# Sheet2.net
KiCad netlist of a schematic drawn in Altium Designer
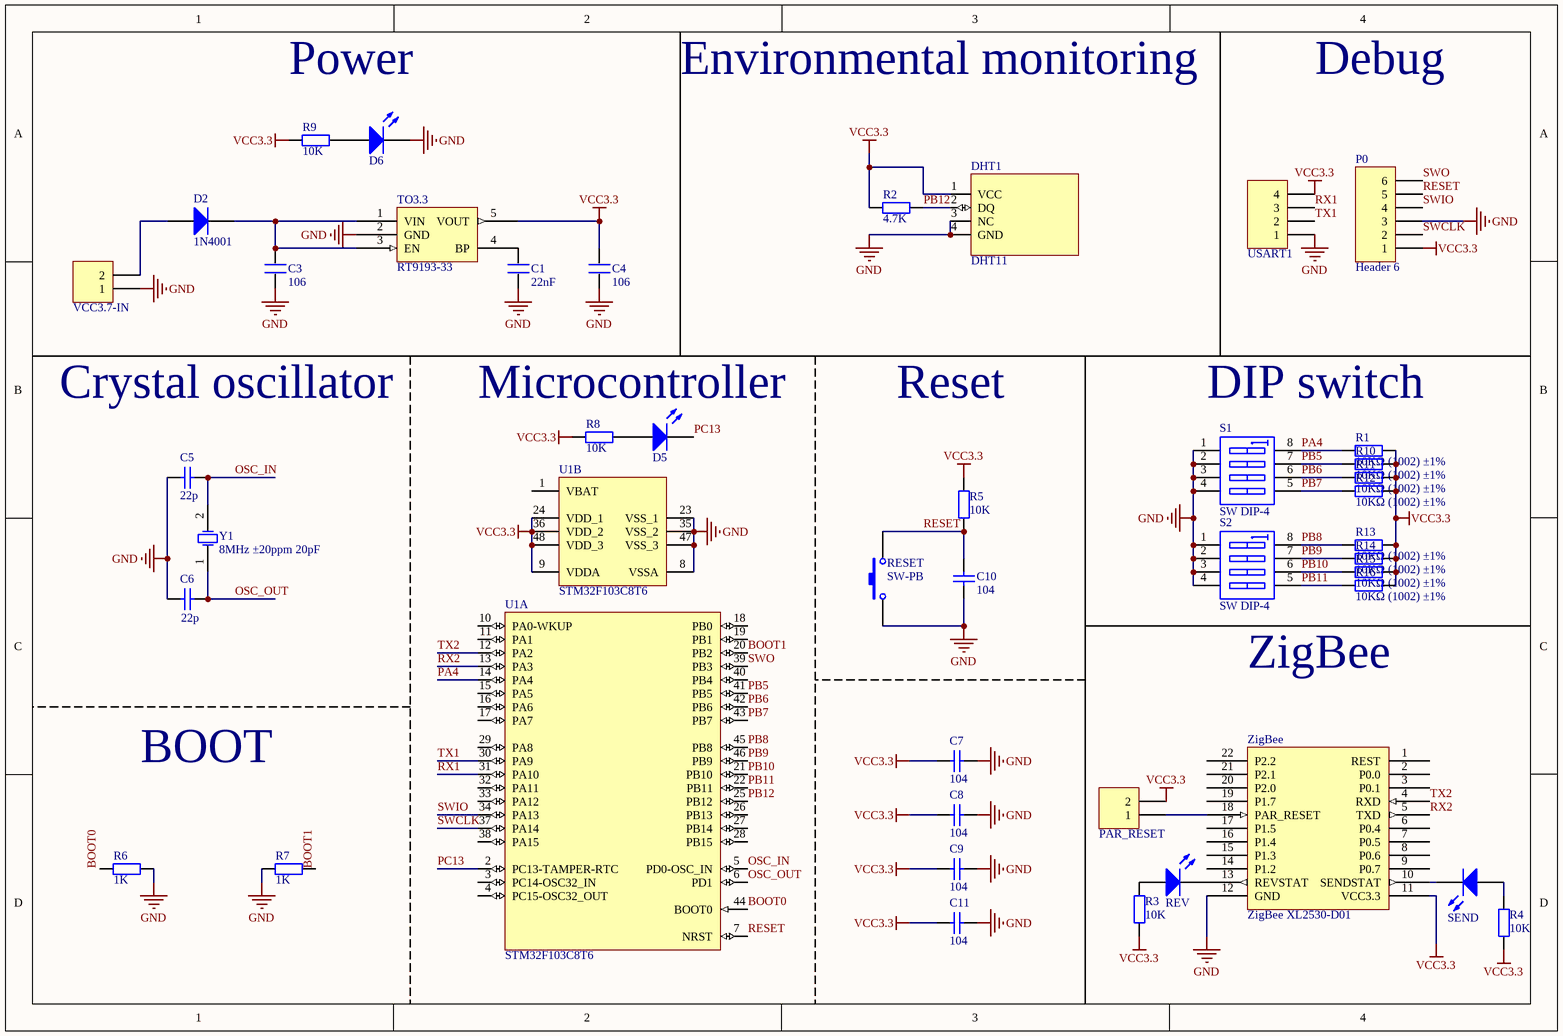
[diagram p0: Sheet2.SchDoc]

(export (version "E")
  (design (tool "Eeschema 10.0.6"))
  (components
    (comp (ref "C1") (value "22nF") (footprint "0805") (libsource (lib "阿波罗STM32F4&F7&H7底板封装库") (part "C")))
    (comp (ref "C3") (value "106") (footprint "0805") (libsource (lib "阿波罗STM32F4&F7&H7底板封装库") (part "C")))
    (comp (ref "C4") (value "106") (footprint "0805") (libsource (lib "阿波罗STM32F4&F7&H7底板封装库") (part "C")))
    (comp (ref "C5")
      (value "22p")
      (footprint "C-RAD-0805")
      (description "无极性电容")
      (fields (field (name "Comment") "Cap") (field (name "PUBLISHER") "Altium Limited"))
      (libsource (lib "ForSTM32") (part "Cap"))
    )
    (comp (ref "C6")
      (value "22p")
      (footprint "C-RAD-0805")
      (description "无极性电容")
      (fields (field (name "Comment") "Cap") (field (name "PUBLISHER") "Altium Limited"))
      (libsource (lib "ForSTM32") (part "Cap"))
    )
    (comp (ref "C7")
      (value "104")
      (footprint "C-RAD-0805")
      (description "无极性电容")
      (fields (field (name "Comment") "Cap") (field (name "PUBLISHER") "Altium Limited"))
      (libsource (lib "ForSTM32") (part "Cap"))
    )
    (comp (ref "C8")
      (value "104")
      (footprint "C-RAD-0805")
      (description "无极性电容")
      (fields (field (name "Comment") "Cap") (field (name "PUBLISHER") "Altium Limited"))
      (libsource (lib "ForSTM32") (part "Cap"))
    )
    (comp (ref "C9")
      (value "104")
      (footprint "C-RAD-0805")
      (description "无极性电容")
      (fields (field (name "Comment") "Cap") (field (name "PUBLISHER") "Altium Limited"))
      (libsource (lib "ForSTM32") (part "Cap"))
    )
    (comp (ref "C10")
      (value "104")
      (footprint "C-RAD-0805")
      (description "无极性电容")
      (fields (field (name "Comment") "Cap") (field (name "PUBLISHER") "Altium Limited"))
      (libsource (lib "ForSTM32") (part "Cap"))
    )
    (comp (ref "C11")
      (value "104")
      (footprint "C-RAD-0805")
      (description "无极性电容")
      (fields (field (name "Comment") "Cap") (field (name "PUBLISHER") "Altium Limited"))
      (libsource (lib "ForSTM32") (part "Cap"))
    )
    (comp (ref "D2")
      (value "Diode")
      (footprint "DIODE-1206")
      (description "二极管")
      (fields (field (name "TYPE") "1N4001") (field (name "PUBLISHER") "Altium Limited"))
      (libsource (lib "ForSTM32") (part "Diode"))
    )
    (comp (ref "D5")
      (value "LED0")
      (footprint "LED_0805")
      (description "发光二极管")
      (fields (field (name "PUBLISHER") "Altium Limited"))
      (libsource (lib "ForSTM32") (part "LED0"))
    )
    (comp (ref "D6")
      (value "LED0")
      (footprint "LED_0805")
      (description "发光二极管")
      (fields (field (name "PUBLISHER") "Altium Limited"))
      (libsource (lib "ForSTM32") (part "LED0"))
    )
    (comp (ref "DHT1") (value "DHT11") (footprint "DTH11") (libsource (lib "我的元件库") (part "DHT11")))
    (comp (ref "P0")
      (value "Header 6")
      (footprint "HDR1X6")
      (description "Header, 6-Pin")
      (fields (field (name "PUBLISHER") "Altium Limited"))
      (libsource (lib "Miscellaneous Connectors") (part "Header 6"))
    )
    (comp (ref "PAR_RESET")
      (value "Header 2")
      (footprint "HDR2X1_A")
      (description "接插件")
      (fields (field (name "PUBLISHER") "Altium Limited"))
      (libsource (lib "ForSTM32") (part "Header 2"))
    )
    (comp (ref "R1")
      (value "10KΩ (1002) ±1%")
      (footprint "0805_R")
      (description "贴片电阻")
      (libsource (lib "Miscellaneous Devices LC") (part "0805 10KΩ (1002) 1%"))
    )
    (comp (ref "R2")
      (value "4.7K")
      (footprint "0805-1")
      (description "贴片电阻")
      (fields (field (name "Comment") "Res1") (field (name "PUBLISHER") "Altium Limited"))
      (libsource (lib "ForSTM32") (part "Res1"))
    )
    (comp (ref "R3")
      (value "10K")
      (footprint "0805-1")
      (description "贴片电阻")
      (fields (field (name "Comment") "Res1") (field (name "PUBLISHER") "Altium Limited"))
      (libsource (lib "") (part "Res1_1"))
    )
    (comp (ref "R4")
      (value "10K")
      (footprint "0805-1")
      (description "贴片电阻")
      (fields (field (name "Comment") "Res1") (field (name "PUBLISHER") "Altium Limited"))
      (libsource (lib "") (part "Res1_1"))
    )
    (comp (ref "R5")
      (value "10K")
      (footprint "0805-1")
      (description "贴片电阻")
      (fields (field (name "Comment") "Res1") (field (name "PUBLISHER") "Altium Limited"))
      (libsource (lib "") (part "Res1_1"))
    )
    (comp (ref "R6")
      (value "1K")
      (footprint "0805-1")
      (description "贴片电阻")
      (fields (field (name "Comment") "Res1") (field (name "PUBLISHER") "Altium Limited"))
      (libsource (lib "ForSTM32") (part "Res1"))
    )
    (comp (ref "R7")
      (value "1K")
      (footprint "0805-1")
      (description "贴片电阻")
      (fields (field (name "Comment") "Res1") (field (name "PUBLISHER") "Altium Limited"))
      (libsource (lib "ForSTM32") (part "Res1"))
    )
    (comp (ref "R8")
      (value "10K")
      (footprint "0805-1")
      (description "贴片电阻")
      (fields (field (name "Comment") "Res1") (field (name "PUBLISHER") "Altium Limited"))
      (libsource (lib "ForSTM32") (part "Res1"))
    )
    (comp (ref "R9")
      (value "10K")
      (footprint "0805-1")
      (description "贴片电阻")
      (fields (field (name "Comment") "Res1") (field (name "PUBLISHER") "Altium Limited"))
      (libsource (lib "ForSTM32") (part "Res1"))
    )
    (comp (ref "R10")
      (value "10KΩ (1002) ±1%")
      (footprint "0805_R")
      (description "贴片电阻")
      (libsource (lib "Miscellaneous Devices LC") (part "0805 10KΩ (1002) 1%"))
    )
    (comp (ref "R11")
      (value "10KΩ (1002) ±1%")
      (footprint "0805_R")
      (description "贴片电阻")
      (libsource (lib "Miscellaneous Devices LC") (part "0805 10KΩ (1002) 1%"))
    )
    (comp (ref "R12")
      (value "10KΩ (1002) ±1%")
      (footprint "0805_R")
      (description "贴片电阻")
      (libsource (lib "Miscellaneous Devices LC") (part "0805 10KΩ (1002) 1%"))
    )
    (comp (ref "R13")
      (value "10KΩ (1002) ±1%")
      (footprint "0805_R")
      (description "贴片电阻")
      (libsource (lib "Miscellaneous Devices LC") (part "0805 10KΩ (1002) 1%"))
    )
    (comp (ref "R14")
      (value "10KΩ (1002) ±1%")
      (footprint "0805_R")
      (description "贴片电阻")
      (libsource (lib "Miscellaneous Devices LC") (part "0805 10KΩ (1002) 1%"))
    )
    (comp (ref "R15")
      (value "10KΩ (1002) ±1%")
      (footprint "0805_R")
      (description "贴片电阻")
      (libsource (lib "Miscellaneous Devices LC") (part "0805 10KΩ (1002) 1%"))
    )
    (comp (ref "R16")
      (value "10KΩ (1002) ±1%")
      (footprint "0805_R")
      (description "贴片电阻")
      (libsource (lib "Miscellaneous Devices LC") (part "0805 10KΩ (1002) 1%"))
    )
    (comp (ref "RESET")
      (value "SW-PB")
      (footprint "SW_PB2_A1")
      (description "微动开关")
      (fields (field (name "PUBLISHER") "Altium Limited"))
      (libsource (lib "ForSTM32") (part "SW-PB"))
    )
    (comp (ref "REV")
      (value "LED0")
      (footprint "LED_0805")
      (description "发光二极管")
      (fields (field (name "PUBLISHER") "Altium Limited"))
      (libsource (lib "ForSTM32") (part "LED0"))
    )
    (comp (ref "S1")
      (value "SW DIP-4")
      (footprint "SO8_xl")
      (description "DIP Switch, 4 Position, SPST")
      (fields (field (name "PUBLISHER") "Altium Limited"))
      (libsource (lib "Miscellaneous Devices") (part "SW DIP-4"))
    )
    (comp (ref "S2")
      (value "SW DIP-4")
      (footprint "SO8_xl")
      (description "DIP Switch, 4 Position, SPST")
      (fields (field (name "PUBLISHER") "Altium Limited"))
      (libsource (lib "Miscellaneous Devices") (part "SW DIP-4"))
    )
    (comp (ref "SEND")
      (value "LED0")
      (footprint "LED_0805")
      (description "发光二极管")
      (fields (field (name "PUBLISHER") "Altium Limited"))
      (libsource (lib "ForSTM32") (part "LED0"))
    )
    (comp (ref "TO3.3")
      (value "RT9193-33")
      (footprint "LC-SOT-23-5")
      (libsource (lib "我的元件库") (part "RT9193-33"))
    )
    (comp (ref "U1")
      (value "STM32F103C8T6")
      (footprint "LQFP-48_7x7x05P")
      (description "ARM")
      (libsource (lib "Miscellaneous Devices LC") (part "STM32F103C8T6"))
    )
    (comp (ref "USART1")
      (value "Header 4")
      (footprint "HDR4X1_A")
      (description "接插件")
      (fields (field (name "PUBLISHER") "Altium Limited"))
      (libsource (lib "ForSTM32") (part "Header 4"))
    )
    (comp (ref "VCC3.7-IN")
      (value "Header 2")
      (footprint "HDR2X1_A")
      (description "接插件")
      (fields (field (name "PUBLISHER") "Altium Limited"))
      (libsource (lib "ForSTM32") (part "Header 2"))
    )
    (comp (ref "Y1")
      (value "8MHz ±20ppm 20pF")
      (footprint "SMD-5032_2P")
      (description "贴片晶振")
      (libsource (lib "Miscellaneous Devices LC") (part "SMD-5032_2P 8MHz 20ppm 20pF"))
    )
    (comp (ref "ZigBee")
      (value "ZigBee XL2530-D01")
      (footprint "ZigBeeXL2530-D01")
      (libsource (lib "我的元件库") (part "ZigBee XL2530-D01"))
    )
  )
  (nets
    (net (code "1") (name "/BOOT0") (class "Default")
      (node (ref "R6") (pin "1") (pinfunction "1_1") (pintype "passive"))
      (node (ref "U1") (pin "44") (pinfunction "BOOT0_44") (pintype "input"))
    )
    (net (code "2") (name "/BOOT1") (class "Default")
      (node (ref "R7") (pin "2") (pinfunction "2_2") (pintype "passive"))
      (node (ref "U1") (pin "20") (pinfunction "PB2_20") (pintype "bidirectional"))
    )
    (net (code "3") (name "/OSC_IN") (class "Default")
      (node (ref "C5") (pin "2") (pinfunction "2_2") (pintype "passive"))
      (node (ref "U1") (pin "5") (pinfunction "PD0-OSC_IN_5") (pintype "bidirectional"))
      (node (ref "Y1") (pin "2") (pinfunction "OSC2_2") (pintype "passive"))
    )
    (net (code "4") (name "/OSC_OUT") (class "Default")
      (node (ref "C6") (pin "2") (pinfunction "2_2") (pintype "passive"))
      (node (ref "U1") (pin "6") (pinfunction "PD1_6") (pintype "bidirectional"))
      (node (ref "Y1") (pin "1") (pinfunction "OSC1_1") (pintype "passive"))
    )
    (net (code "5") (name "/PA4") (class "Default")
      (node (ref "R1") (pin "1") (pinfunction "1_1") (pintype "passive"))
      (node (ref "S1") (pin "8") (pinfunction "B1_8") (pintype "passive"))
      (node (ref "U1") (pin "14") (pinfunction "PA4_14") (pintype "bidirectional"))
    )
    (net (code "6") (name "/PB5") (class "Default")
      (node (ref "R10") (pin "1") (pinfunction "1_1") (pintype "passive"))
      (node (ref "S1") (pin "7") (pinfunction "B2_7") (pintype "passive"))
      (node (ref "U1") (pin "41") (pinfunction "PB5_41") (pintype "bidirectional"))
    )
    (net (code "7") (name "/PB6") (class "Default")
      (node (ref "R11") (pin "1") (pinfunction "1_1") (pintype "passive"))
      (node (ref "S1") (pin "6") (pinfunction "B3_6") (pintype "passive"))
      (node (ref "U1") (pin "42") (pinfunction "PB6_42") (pintype "bidirectional"))
    )
    (net (code "8") (name "/PB7") (class "Default")
      (node (ref "R12") (pin "1") (pinfunction "1_1") (pintype "passive"))
      (node (ref "S1") (pin "5") (pinfunction "B4_5") (pintype "passive"))
      (node (ref "U1") (pin "43") (pinfunction "PB7_43") (pintype "bidirectional"))
    )
    (net (code "9") (name "/PB8") (class "Default")
      (node (ref "R13") (pin "1") (pinfunction "1_1") (pintype "passive"))
      (node (ref "S2") (pin "8") (pinfunction "B1_8") (pintype "passive"))
      (node (ref "U1") (pin "45") (pinfunction "PB8_45") (pintype "bidirectional"))
    )
    (net (code "10") (name "/PB9") (class "Default")
      (node (ref "R14") (pin "1") (pinfunction "1_1") (pintype "passive"))
      (node (ref "S2") (pin "7") (pinfunction "B2_7") (pintype "passive"))
      (node (ref "U1") (pin "46") (pinfunction "PB9_46") (pintype "bidirectional"))
    )
    (net (code "11") (name "/PB10") (class "Default")
      (node (ref "R15") (pin "1") (pinfunction "1_1") (pintype "passive"))
      (node (ref "S2") (pin "6") (pinfunction "B3_6") (pintype "passive"))
      (node (ref "U1") (pin "21") (pinfunction "PB10_21") (pintype "bidirectional"))
    )
    (net (code "12") (name "/PB11") (class "Default")
      (node (ref "R16") (pin "1") (pinfunction "1_1") (pintype "passive"))
      (node (ref "S2") (pin "5") (pinfunction "B4_5") (pintype "passive"))
      (node (ref "U1") (pin "22") (pinfunction "PB11_22") (pintype "bidirectional"))
    )
    (net (code "13") (name "/PB12") (class "Default")
      (node (ref "DHT1") (pin "2") (pinfunction "DQ_2") (pintype "bidirectional"))
      (node (ref "R2") (pin "2") (pinfunction "2_2") (pintype "passive"))
      (node (ref "U1") (pin "25") (pinfunction "PB12_25") (pintype "bidirectional"))
    )
    (net (code "14") (name "/PC13") (class "Default")
      (node (ref "D5") (pin "2") (pinfunction "K_2") (pintype "passive"))
      (node (ref "U1") (pin "2") (pinfunction "PC13-TAMPER-RTC_2") (pintype "bidirectional"))
    )
    (net (code "15") (name "/RESET") (class "Default")
      (node (ref "C10") (pin "1") (pinfunction "1_1") (pintype "passive"))
      (node (ref "P0") (pin "5") (pinfunction "5_5") (pintype "passive"))
      (node (ref "R5") (pin "1") (pinfunction "1_1") (pintype "passive"))
      (node (ref "RESET") (pin "2") (pinfunction "2_2") (pintype "passive"))
      (node (ref "U1") (pin "7") (pinfunction "NRST_7") (pintype "bidirectional"))
    )
    (net (code "16") (name "/RX1") (class "Default")
      (node (ref "U1") (pin "31") (pinfunction "PA10_31") (pintype "bidirectional"))
      (node (ref "USART1") (pin "3") (pinfunction "3_3") (pintype "passive"))
    )
    (net (code "17") (name "/RX2") (class "Default")
      (node (ref "U1") (pin "13") (pinfunction "PA3_13") (pintype "bidirectional"))
      (node (ref "ZigBee") (pin "5") (pinfunction "TXD_5") (pintype "output"))
    )
    (net (code "18") (name "/SWCLK") (class "Default")
      (node (ref "P0") (pin "2") (pinfunction "2_2") (pintype "passive"))
      (node (ref "U1") (pin "37") (pinfunction "PA14_37") (pintype "bidirectional"))
    )
    (net (code "19") (name "/SWIO") (class "Default")
      (node (ref "P0") (pin "4") (pinfunction "4_4") (pintype "passive"))
      (node (ref "U1") (pin "34") (pinfunction "PA13_34") (pintype "bidirectional"))
    )
    (net (code "20") (name "/SWO") (class "Default")
      (node (ref "P0") (pin "6") (pinfunction "6_6") (pintype "passive"))
      (node (ref "U1") (pin "39") (pinfunction "PB3_39") (pintype "bidirectional"))
    )
    (net (code "21") (name "/TX1") (class "Default")
      (node (ref "U1") (pin "30") (pinfunction "PA9_30") (pintype "bidirectional"))
      (node (ref "USART1") (pin "2") (pinfunction "2_2") (pintype "passive"))
    )
    (net (code "22") (name "/TX2") (class "Default")
      (node (ref "U1") (pin "12") (pinfunction "PA2_12") (pintype "bidirectional"))
      (node (ref "ZigBee") (pin "4") (pinfunction "RXD_4") (pintype "input"))
    )
    (net (code "23") (name "GND") (class "Default")
      (node (ref "C1") (pin "1") (pintype "passive"))
      (node (ref "C10") (pin "2") (pinfunction "2_2") (pintype "passive"))
      (node (ref "C11") (pin "2") (pinfunction "2_2") (pintype "passive"))
      (node (ref "C3") (pin "2") (pintype "passive"))
      (node (ref "C4") (pin "1") (pintype "passive"))
      (node (ref "C5") (pin "1") (pinfunction "1_1") (pintype "passive"))
      (node (ref "C6") (pin "1") (pinfunction "1_1") (pintype "passive"))
      (node (ref "C7") (pin "2") (pinfunction "2_2") (pintype "passive"))
      (node (ref "C8") (pin "2") (pinfunction "2_2") (pintype "passive"))
      (node (ref "C9") (pin "2") (pinfunction "2_2") (pintype "passive"))
      (node (ref "D6") (pin "2") (pinfunction "K_2") (pintype "passive"))
      (node (ref "DHT1") (pin "3") (pinfunction "NC_3") (pintype "passive"))
      (node (ref "DHT1") (pin "4") (pinfunction "GND_4") (pintype "power_in"))
      (node (ref "P0") (pin "3") (pinfunction "3_3") (pintype "passive"))
      (node (ref "R6") (pin "2") (pinfunction "2_2") (pintype "passive"))
      (node (ref "R7") (pin "1") (pinfunction "1_1") (pintype "passive"))
      (node (ref "RESET") (pin "1") (pinfunction "1_1") (pintype "passive"))
      (node (ref "S1") (pin "1") (pinfunction "A1_1") (pintype "passive"))
      (node (ref "S1") (pin "2") (pinfunction "A2_2") (pintype "passive"))
      (node (ref "S1") (pin "3") (pinfunction "A3_3") (pintype "passive"))
      (node (ref "S1") (pin "4") (pinfunction "A4_4") (pintype "passive"))
      (node (ref "S2") (pin "1") (pinfunction "A1_1") (pintype "passive"))
      (node (ref "S2") (pin "2") (pinfunction "A2_2") (pintype "passive"))
      (node (ref "S2") (pin "3") (pinfunction "A3_3") (pintype "passive"))
      (node (ref "S2") (pin "4") (pinfunction "A4_4") (pintype "passive"))
      (node (ref "TO3.3") (pin "2") (pinfunction "GND_2") (pintype "power_in"))
      (node (ref "U1") (pin "23") (pinfunction "VSS_1_23") (pintype "power_in"))
      (node (ref "U1") (pin "35") (pinfunction "VSS_2_35") (pintype "power_in"))
      (node (ref "U1") (pin "47") (pinfunction "VSS_3_47") (pintype "power_in"))
      (node (ref "U1") (pin "8") (pinfunction "VSSA_8") (pintype "power_in"))
      (node (ref "USART1") (pin "1") (pinfunction "1_1") (pintype "passive"))
      (node (ref "VCC3.7-IN") (pin "1") (pinfunction "1_1") (pintype "passive"))
      (node (ref "ZigBee") (pin "12") (pinfunction "GND_12") (pintype "passive"))
    )
    (net (code "24") (name "Net-(D2-A)") (class "Default")
      (node (ref "D2") (pin "1") (pinfunction "A_1") (pintype "passive"))
      (node (ref "VCC3.7-IN") (pin "2") (pinfunction "2_2") (pintype "passive"))
    )
    (net (code "25") (name "Net-(D2-K)") (class "Default")
      (node (ref "C3") (pin "1") (pintype "passive"))
      (node (ref "D2") (pin "2") (pinfunction "K_2") (pintype "passive"))
      (node (ref "TO3.3") (pin "1") (pinfunction "VIN_1") (pintype "power_in"))
      (node (ref "TO3.3") (pin "3") (pinfunction "EN_3") (pintype "input"))
    )
    (net (code "26") (name "Net-(D5-A)") (class "Default")
      (node (ref "D5") (pin "1") (pinfunction "A_1") (pintype "passive"))
      (node (ref "R8") (pin "2") (pinfunction "2_2") (pintype "passive"))
    )
    (net (code "27") (name "Net-(D6-A)") (class "Default")
      (node (ref "D6") (pin "1") (pinfunction "A_1") (pintype "passive"))
      (node (ref "R9") (pin "2") (pinfunction "2_2") (pintype "passive"))
    )
    (net (code "28") (name "Net-(REV-A)") (class "Default")
      (node (ref "R3") (pin "2") (pinfunction "2_2") (pintype "passive"))
      (node (ref "REV") (pin "1") (pinfunction "A_1") (pintype "passive"))
    )
    (net (code "29") (name "Net-(REV-K)") (class "Default")
      (node (ref "REV") (pin "2") (pinfunction "K_2") (pintype "passive"))
      (node (ref "ZigBee") (pin "13") (pinfunction "REVSTAT_13") (pintype "output"))
    )
    (net (code "30") (name "Net-(SEND-A)") (class "Default")
      (node (ref "R4") (pin "2") (pinfunction "2_2") (pintype "passive"))
      (node (ref "SEND") (pin "1") (pinfunction "A_1") (pintype "passive"))
    )
    (net (code "31") (name "Net-(SEND-K)") (class "Default")
      (node (ref "SEND") (pin "2") (pinfunction "K_2") (pintype "passive"))
      (node (ref "ZigBee") (pin "10") (pinfunction "SENDSTAT_10") (pintype "output"))
    )
    (net (code "32") (name "Net-(TO3.3-BP)") (class "Default")
      (node (ref "C1") (pin "2") (pintype "passive"))
      (node (ref "TO3.3") (pin "4") (pinfunction "BP_4") (pintype "passive"))
    )
    (net (code "33") (name "Net-(ZigBee-PAR_RESET)") (class "Default")
      (node (ref "PAR_RESET") (pin "1") (pinfunction "1_1") (pintype "passive"))
      (node (ref "ZigBee") (pin "18") (pinfunction "PAR_RESET_18") (pintype "input"))
    )
    (net (code "34") (name "VCC3.3") (class "Default")
      (node (ref "C11") (pin "1") (pinfunction "1_1") (pintype "passive"))
      (node (ref "C4") (pin "2") (pintype "passive"))
      (node (ref "C7") (pin "1") (pinfunction "1_1") (pintype "passive"))
      (node (ref "C8") (pin "1") (pinfunction "1_1") (pintype "passive"))
      (node (ref "C9") (pin "1") (pinfunction "1_1") (pintype "passive"))
      (node (ref "DHT1") (pin "1") (pinfunction "VCC_1") (pintype "power_in"))
      (node (ref "P0") (pin "1") (pinfunction "1_1") (pintype "passive"))
      (node (ref "PAR_RESET") (pin "2") (pinfunction "2_2") (pintype "passive"))
      (node (ref "R1") (pin "2") (pinfunction "2_2") (pintype "passive"))
      (node (ref "R10") (pin "2") (pinfunction "2_2") (pintype "passive"))
      (node (ref "R11") (pin "2") (pinfunction "2_2") (pintype "passive"))
      (node (ref "R12") (pin "2") (pinfunction "2_2") (pintype "passive"))
      (node (ref "R13") (pin "2") (pinfunction "2_2") (pintype "passive"))
      (node (ref "R14") (pin "2") (pinfunction "2_2") (pintype "passive"))
      (node (ref "R15") (pin "2") (pinfunction "2_2") (pintype "passive"))
      (node (ref "R16") (pin "2") (pinfunction "2_2") (pintype "passive"))
      (node (ref "R2") (pin "1") (pinfunction "1_1") (pintype "passive"))
      (node (ref "R3") (pin "1") (pinfunction "1_1") (pintype "passive"))
      (node (ref "R4") (pin "1") (pinfunction "1_1") (pintype "passive"))
      (node (ref "R5") (pin "2") (pinfunction "2_2") (pintype "passive"))
      (node (ref "R8") (pin "1") (pinfunction "1_1") (pintype "passive"))
      (node (ref "R9") (pin "1") (pinfunction "1_1") (pintype "passive"))
      (node (ref "TO3.3") (pin "5") (pinfunction "VOUT_5") (pintype "output"))
      (node (ref "U1") (pin "24") (pinfunction "VDD_1_24") (pintype "power_in"))
      (node (ref "U1") (pin "36") (pinfunction "VDD_2_36") (pintype "power_in"))
      (node (ref "U1") (pin "48") (pinfunction "VDD_3_48") (pintype "power_in"))
      (node (ref "U1") (pin "9") (pinfunction "VDDA_9") (pintype "power_in"))
      (node (ref "USART1") (pin "4") (pinfunction "4_4") (pintype "passive"))
      (node (ref "ZigBee") (pin "11") (pinfunction "VCC3.3_11") (pintype "passive"))
    )
    (net (code "35") (name "unconnected-(U1A-PA0-WKUP-Pad10)") (class "Default")
      (node (ref "U1") (pin "10") (pinfunction "PA0-WKUP_10") (pintype "bidirectional"))
    )
    (net (code "36") (name "unconnected-(U1A-PA1-Pad11)") (class "Default")
      (node (ref "U1") (pin "11") (pinfunction "PA1_11") (pintype "bidirectional"))
    )
    (net (code "37") (name "unconnected-(U1A-PA5-Pad15)") (class "Default")
      (node (ref "U1") (pin "15") (pinfunction "PA5_15") (pintype "bidirectional"))
    )
    (net (code "38") (name "unconnected-(U1A-PA6-Pad16)") (class "Default")
      (node (ref "U1") (pin "16") (pinfunction "PA6_16") (pintype "bidirectional"))
    )
    (net (code "39") (name "unconnected-(U1A-PA7-Pad17)") (class "Default")
      (node (ref "U1") (pin "17") (pinfunction "PA7_17") (pintype "bidirectional"))
    )
    (net (code "40") (name "unconnected-(U1A-PA8-Pad29)") (class "Default")
      (node (ref "U1") (pin "29") (pinfunction "PA8_29") (pintype "bidirectional"))
    )
    (net (code "41") (name "unconnected-(U1A-PA11-Pad32)") (class "Default")
      (node (ref "U1") (pin "32") (pinfunction "PA11_32") (pintype "bidirectional"))
    )
    (net (code "42") (name "unconnected-(U1A-PA12-Pad33)") (class "Default")
      (node (ref "U1") (pin "33") (pinfunction "PA12_33") (pintype "bidirectional"))
    )
    (net (code "43") (name "unconnected-(U1A-PA15-Pad38)") (class "Default")
      (node (ref "U1") (pin "38") (pinfunction "PA15_38") (pintype "bidirectional"))
    )
    (net (code "44") (name "unconnected-(U1A-PB0-Pad18)") (class "Default")
      (node (ref "U1") (pin "18") (pinfunction "PB0_18") (pintype "bidirectional"))
    )
    (net (code "45") (name "unconnected-(U1A-PB1-Pad19)") (class "Default")
      (node (ref "U1") (pin "19") (pinfunction "PB1_19") (pintype "bidirectional"))
    )
    (net (code "46") (name "unconnected-(U1A-PB4-Pad40)") (class "Default")
      (node (ref "U1") (pin "40") (pinfunction "PB4_40") (pintype "bidirectional"))
    )
    (net (code "47") (name "unconnected-(U1A-PB13-Pad26)") (class "Default")
      (node (ref "U1") (pin "26") (pinfunction "PB13_26") (pintype "bidirectional"))
    )
    (net (code "48") (name "unconnected-(U1A-PB14-Pad27)") (class "Default")
      (node (ref "U1") (pin "27") (pinfunction "PB14_27") (pintype "bidirectional"))
    )
    (net (code "49") (name "unconnected-(U1A-PB15-Pad28)") (class "Default")
      (node (ref "U1") (pin "28") (pinfunction "PB15_28") (pintype "bidirectional"))
    )
    (net (code "50") (name "unconnected-(U1A-PC14-OSC32_IN-Pad3)") (class "Default")
      (node (ref "U1") (pin "3") (pinfunction "PC14-OSC32_IN_3") (pintype "bidirectional"))
    )
    (net (code "51") (name "unconnected-(U1A-PC15-OSC32_OUT-Pad4)") (class "Default")
      (node (ref "U1") (pin "4") (pinfunction "PC15-OSC32_OUT_4") (pintype "bidirectional"))
    )
    (net (code "52") (name "unconnected-(U1B-VBAT-Pad1)") (class "Default")
      (node (ref "U1") (pin "1") (pinfunction "VBAT_1") (pintype "power_in"))
    )
    (net (code "53") (name "unconnected-(ZigBee-P0.0-Pad2)") (class "Default")
      (node (ref "ZigBee") (pin "2") (pinfunction "P0.0_2") (pintype "passive"))
    )
    (net (code "54") (name "unconnected-(ZigBee-P0.1-Pad3)") (class "Default")
      (node (ref "ZigBee") (pin "3") (pinfunction "P0.1_3") (pintype "passive"))
    )
    (net (code "55") (name "unconnected-(ZigBee-P0.4-Pad6)") (class "Default")
      (node (ref "ZigBee") (pin "6") (pinfunction "P0.4_6") (pintype "passive"))
    )
    (net (code "56") (name "unconnected-(ZigBee-P0.5-Pad7)") (class "Default")
      (node (ref "ZigBee") (pin "7") (pinfunction "P0.5_7") (pintype "passive"))
    )
    (net (code "57") (name "unconnected-(ZigBee-P0.6-Pad8)") (class "Default")
      (node (ref "ZigBee") (pin "8") (pinfunction "P0.6_8") (pintype "passive"))
    )
    (net (code "58") (name "unconnected-(ZigBee-P0.7-Pad9)") (class "Default")
      (node (ref "ZigBee") (pin "9") (pinfunction "P0.7_9") (pintype "passive"))
    )
    (net (code "59") (name "unconnected-(ZigBee-P1.2-Pad14)") (class "Default")
      (node (ref "ZigBee") (pin "14") (pinfunction "P1.2_14") (pintype "passive"))
    )
    (net (code "60") (name "unconnected-(ZigBee-P1.3-Pad15)") (class "Default")
      (node (ref "ZigBee") (pin "15") (pinfunction "P1.3_15") (pintype "passive"))
    )
    (net (code "61") (name "unconnected-(ZigBee-P1.4-Pad16)") (class "Default")
      (node (ref "ZigBee") (pin "16") (pinfunction "P1.4_16") (pintype "passive"))
    )
    (net (code "62") (name "unconnected-(ZigBee-P1.5-Pad17)") (class "Default")
      (node (ref "ZigBee") (pin "17") (pinfunction "P1.5_17") (pintype "passive"))
    )
    (net (code "63") (name "unconnected-(ZigBee-P1.7-Pad19)") (class "Default")
      (node (ref "ZigBee") (pin "19") (pinfunction "P1.7_19") (pintype "passive"))
    )
    (net (code "64") (name "unconnected-(ZigBee-P2.0-Pad20)") (class "Default")
      (node (ref "ZigBee") (pin "20") (pinfunction "P2.0_20") (pintype "passive"))
    )
    (net (code "65") (name "unconnected-(ZigBee-P2.1-Pad21)") (class "Default")
      (node (ref "ZigBee") (pin "21") (pinfunction "P2.1_21") (pintype "passive"))
    )
    (net (code "66") (name "unconnected-(ZigBee-P2.2-Pad22)") (class "Default")
      (node (ref "ZigBee") (pin "22") (pinfunction "P2.2_22") (pintype "passive"))
    )
    (net (code "67") (name "unconnected-(ZigBee-REST-Pad1)") (class "Default")
      (node (ref "ZigBee") (pin "1") (pinfunction "REST_1") (pintype "passive"))
    )
  )
)
